# LTM-2405.net
KiCad netlist of a schematic drawn in Altium Designer
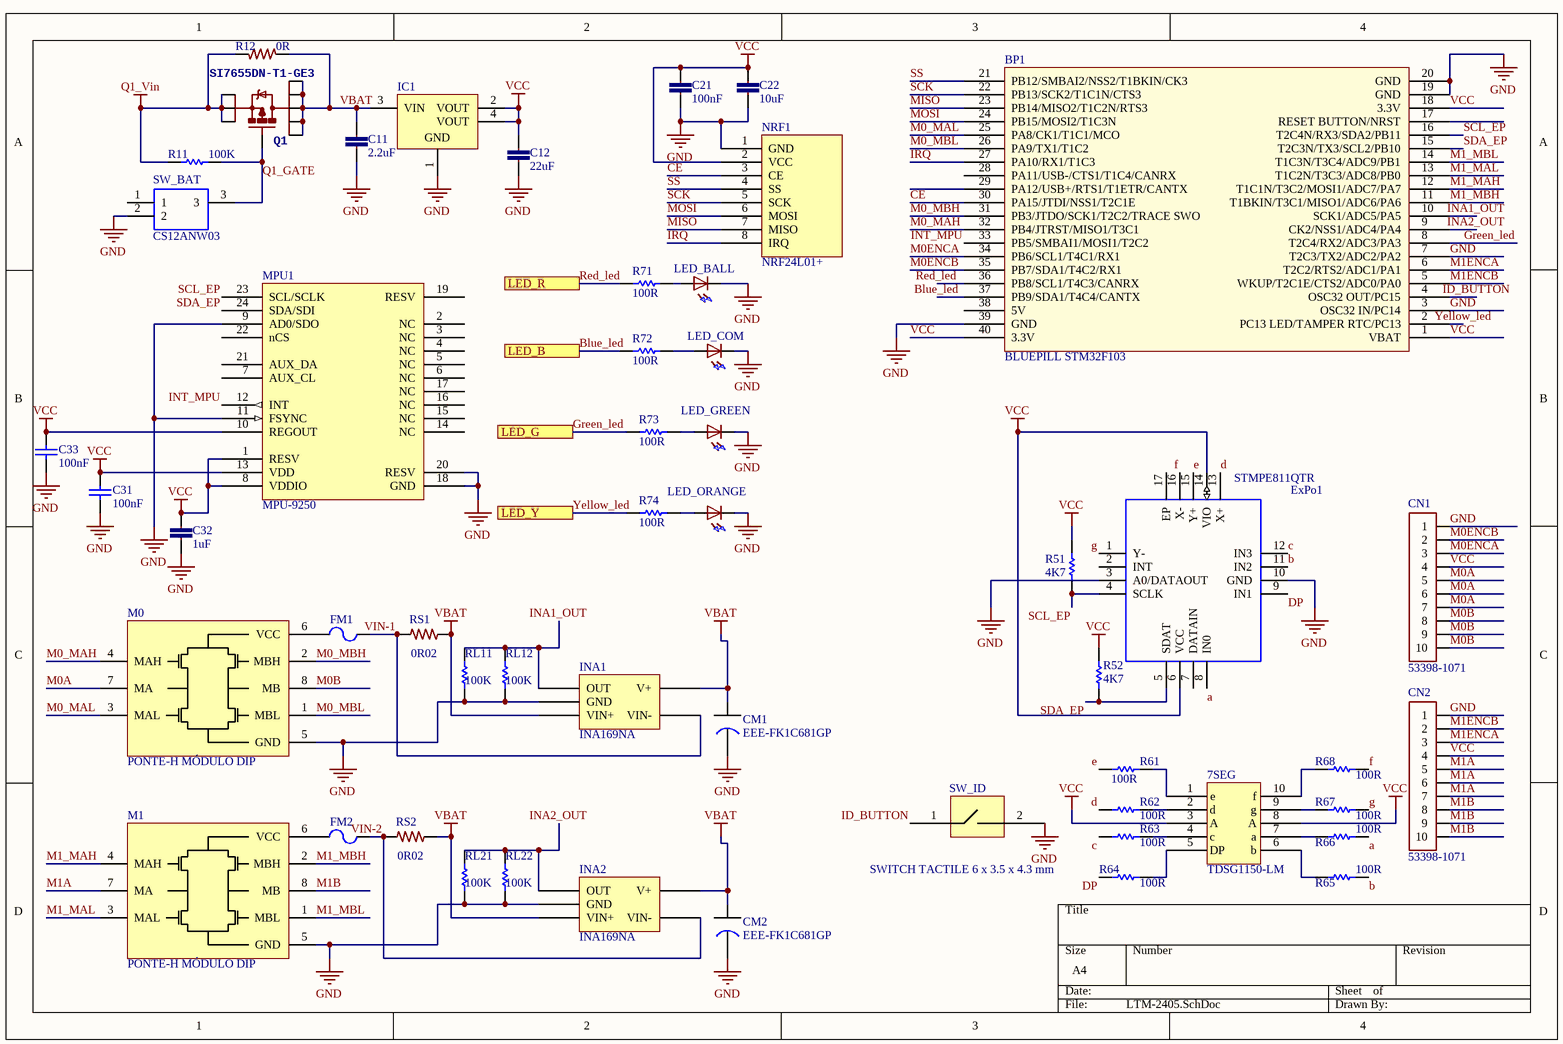
[diagram p0: LTM-2405.SchDoc]

(export (version "E")
  (design (tool "Eeschema 10.0.6"))
  (components
    (comp (ref "7SEG")
      (value "TDSG1150-LM")
      (footprint "7seg-pcb")
      (libsource (lib "7seg") (part "TDSG1150-LM"))
    )
    (comp (ref "BP1")
      (value "BLUEPILL STM32F103")
      (footprint "BLUEPILL-PCB")
      (description "STM32 Blue Pill Development Module")
      (libsource (lib "IMBEL") (part "BLUEPILL-SCH"))
    )
    (comp (ref "C11")
      (value "2.2uF")
      (footprint "1206-CAP")
      (description "CAP CER 2.2UF 50V X7R 1206")
      (fields (field (name "PART NO") "UMK316B7225KL-T"))
      (libsource (lib "IMBEL") (part "CAPACITOR"))
    )
    (comp (ref "C12")
      (value "22uF")
      (footprint "1206-CAP")
      (description "CAP CER 22UF 6.3V 20% X5R 1206")
      (fields (field (name "PART NO") "C3216X5R0J226M085AC"))
      (libsource (lib "IMBEL") (part "CC1206-22uF-6.3V-1"))
    )
    (comp (ref "C21")
      (value "100nF")
      (footprint "0402-CAP")
      (description "CAP CER 0.1UF 50V 10% X7R 0402")
      (fields (field (name "PART NO") "C1005X7R1H104K050BB"))
      (libsource (lib "Personal Vault(migrated)") (part "CAPACITOR"))
    )
    (comp (ref "C22")
      (value "10uF")
      (footprint "1210-CAP")
      (description "CAP CER 10UF 50V 20% X5R 1210")
      (fields (field (name "PART NO") "UMK325BJ106MM"))
      (libsource (lib "") (part "CAPACITOR_1"))
    )
    (comp (ref "C31")
      (value "100nF")
      (footprint "CAPC0402(1005)60_N")
      (description "CAP 100nF 10V ±10% 0402 (1005 Metric) Thickness 0.6mm SMD")
      (fields (field (name "TOLERANCE") "Â±10%"))
      (libsource (lib "Integrated_Library - 26.10.18 - 17.40") (part "CMP-1034-02065-1"))
    )
    (comp (ref "C32")
      (value "1uF")
      (footprint "0402-CAP")
      (description "CAP CER 1UF 6.3V 10% X5R 0402")
      (fields (field (name "PART NO") "JMK105BJ105KV-F"))
      (libsource (lib "IMBEL") (part "CAPACITOR"))
    )
    (comp (ref "C33")
      (value "100nF")
      (footprint "CAPC0402(1005)60_N")
      (description "CAP 100nF 10V ±10% 0402 (1005 Metric) Thickness 0.6mm SMD")
      (fields (field (name "TOLERANCE") "Â±10%"))
      (libsource (lib "Integrated_Library - 26.10.18 - 17.40") (part "CMP-1034-02065-1"))
    )
    (comp (ref "CM1")
      (value "EEE-FK1C681GP")
      (footprint "EEE-FK1C681GP")
      (description "Aluminum Electrolytic Capacitors - SMD Al Lytic Cap SMT FK Series 105C")
      (libsource (lib "Schlib1") (part "CAP AL 680UF/16V"))
    )
    (comp (ref "CM2")
      (value "EEE-FK1C681GP")
      (footprint "EEE-FK1C681GP")
      (description "Aluminum Electrolytic Capacitors - SMD Al Lytic Cap SMT FK Series 105C")
      (libsource (lib "Schlib1") (part "CAP AL 680UF/16V"))
    )
    (comp (ref "CN1")
      (value "53398-1071")
      (footprint "53398-10")
      (description "CONN HEADER 10POS 1.25MM VRT SMD")
      (libsource (lib "IMBEL") (part "CON-10"))
    )
    (comp (ref "CN2")
      (value "53398-1071")
      (footprint "53398-10")
      (description "CONN HEADER 10POS 1.25MM VRT SMD")
      (libsource (lib "IMBEL") (part "CON-10"))
    )
    (comp (ref "ExPo1")
      (value "STMPE811QTR")
      (footprint "QFN50P300X300X100-17N-D")
      (description "Interface - I/O Expanders 8-BIT PORT EXPANDER W/ADV TOUCHSCREEN")
      (fields (field (name "RS PART NUMBER") "1658056"))
      (libsource (lib "STMPE811QTR") (part "STMPE811QTR"))
    )
    (comp (ref "FM1")
      (value "MF-MSMF030-2CT-ND")
      (footprint "RESC4632X16N")
      (description "FUSE PTC RESETTBL .30A 30V 1812")
      (libsource (lib "IMBEL") (part "FUSE-SCH"))
    )
    (comp (ref "FM2")
      (value "MF-MSMF030-2CT-ND")
      (footprint "RESC4632X16N")
      (description "FUSE PTC RESETTBL .30A 30V 1812")
      (libsource (lib "IMBEL") (part "FUSE-SCH"))
    )
    (comp (ref "IC1")
      (value "LD1117S33CTR")
      (footprint "SOT-223_N")
      (description "Fixed Low Drop Positive Voltage Regulator, 3.3V, 4-Pin SOT-223, Tape and Reel")
      (libsource (lib "Altium Content Vault") (part "CMP-0244-00307-1"))
    )
    (comp (ref "INA1")
      (value "INA169NA")
      (footprint "SOT95P280X125-5N")
      (description "IC CURRENT MONITOR 0.5% SOT23-5")
      (libsource (lib "IMBEL") (part "ina169"))
    )
    (comp (ref "INA2")
      (value "INA169NA")
      (footprint "SOT95P280X125-5N")
      (description "IC CURRENT MONITOR 0.5% SOT23-5")
      (libsource (lib "IMBEL") (part "ina169"))
    )
    (comp (ref "LED_BALL")
      (value "LED")
      (footprint "LED-5MM-PCB")
      (description "LED 5MM PTH")
      (libsource (lib "IMBEL") (part "LED"))
    )
    (comp (ref "LED_COM")
      (value "LED")
      (footprint "LED-5MM-PCB")
      (description "LED 5MM PTH")
      (libsource (lib "IMBEL") (part "LED"))
    )
    (comp (ref "LED_GREEN")
      (value "LED")
      (footprint "LED-5MM-PCB")
      (description "LED 5MM PTH")
      (libsource (lib "IMBEL") (part "LED"))
    )
    (comp (ref "LED_ORANGE")
      (value "LED")
      (footprint "LED-5MM-PCB")
      (description "LED 5MM PTH")
      (libsource (lib "IMBEL") (part "LED"))
    )
    (comp (ref "M0")
      (value "PONTE-H MÓDULO DIP")
      (footprint "PONTEH-PCB")
      (description "MÓDULO PONTE H DIP ROBOIME")
      (libsource (lib "IMBEL") (part "PONTEH-SCH"))
    )
    (comp (ref "M1")
      (value "PONTE-H MÓDULO DIP")
      (footprint "PONTEH-PCB")
      (description "MÓDULO PONTE H DIP ROBOIME")
      (libsource (lib "IMBEL") (part "PONTEH-SCH"))
    )
    (comp (ref "MPU1")
      (value "MPU-9250")
      (footprint "MPU-9250")
      (description "IMU ACCEL/GYRO/MAG I2C/SPI 24QFN")
      (libsource (lib "IMBEL") (part "Component_1"))
    )
    (comp (ref "NRF1")
      (value "NRF24L01+")
      (footprint "NRF24L01P-PCB")
      (libsource (lib "IMBEL") (part "NRF24-SCH"))
    )
    (comp (ref "Q1")
      (value "SI7655DN-T1-GE3")
      (footprint "SON8")
      (description "MOSFET P-CH 20V D-S PPAK 1212")
      (libsource (lib "IMBEL") (part "MOSFET-PCHANNEL"))
    )
    (comp (ref "R11")
      (value "100K")
      (footprint "RESC0402(1005)_L")
      (description "100K 0.063W 1% 0402 (1005 Metric)  SMD")
      (fields (field (name "POWER") "0.063 W") (field (name "TOLERANCE") "1 %"))
      (libsource (lib "Integrated_Library - 26.10.18 - 17.11") (part "CMP-1011-00736-1"))
    )
    (comp (ref "R12")
      (value "0R")
      (footprint "0402-RES-HD")
      (description "RES 0.0 OHM 1/16W JUMP 0402 SMD")
      (fields (field (name "PART NO") "CRCW04020000Z0ED"))
      (libsource (lib "IMBEL") (part "RESISTOR"))
    )
    (comp (ref "R51")
      (value "4K7")
      (footprint "RESC0402(1005)_L")
      (description "4K7 0.063W 1% 0402 (1005 Metric)  SMD")
      (fields (field (name "POWER") "0.063 W") (field (name "TOLERANCE") "1 %"))
      (libsource (lib "Integrated_Library - 26.10.18 - 17.46") (part "CMP-1011-00586-1"))
    )
    (comp (ref "R52")
      (value "4K7")
      (footprint "RESC0402(1005)_L")
      (description "4K7 0.063W 1% 0402 (1005 Metric)  SMD")
      (fields (field (name "POWER") "0.063 W") (field (name "TOLERANCE") "1 %"))
      (libsource (lib "Integrated_Library - 26.10.18 - 17.46") (part "CMP-1011-00586-1"))
    )
    (comp (ref "R61")
      (value "100R")
      (footprint "RESC0402(1005)_L")
      (description "100R 0.063W 1% 0402 (1005 Metric)  SMD")
      (fields (field (name "TOLERANCE") "1 %") (field (name "POWER") "0.063 W"))
      (libsource (lib "RES_100R") (part "CMP-1011-00397-1"))
    )
    (comp (ref "R62")
      (value "100R")
      (footprint "RESC0402(1005)_L")
      (description "100R 0.063W 1% 0402 (1005 Metric)  SMD")
      (fields (field (name "TOLERANCE") "1 %") (field (name "POWER") "0.063 W"))
      (libsource (lib "RES_100R") (part "CMP-1011-00397-1"))
    )
    (comp (ref "R63")
      (value "100R")
      (footprint "RESC0402(1005)_L")
      (description "100R 0.063W 1% 0402 (1005 Metric)  SMD")
      (fields (field (name "TOLERANCE") "1 %") (field (name "POWER") "0.063 W"))
      (libsource (lib "RES_100R") (part "CMP-1011-00397-1"))
    )
    (comp (ref "R64")
      (value "100R")
      (footprint "RESC0402(1005)_L")
      (description "100R 0.063W 1% 0402 (1005 Metric)  SMD")
      (fields (field (name "TOLERANCE") "1 %") (field (name "POWER") "0.063 W"))
      (libsource (lib "RES_100R") (part "CMP-1011-00397-1"))
    )
    (comp (ref "R65")
      (value "100R")
      (footprint "RESC0402(1005)_L")
      (description "100R 0.063W 1% 0402 (1005 Metric)  SMD")
      (fields (field (name "TOLERANCE") "1 %") (field (name "POWER") "0.063 W"))
      (libsource (lib "RES_100R") (part "CMP-1011-00397-1"))
    )
    (comp (ref "R66")
      (value "100R")
      (footprint "RESC0402(1005)_L")
      (description "100R 0.063W 1% 0402 (1005 Metric)  SMD")
      (fields (field (name "TOLERANCE") "1 %") (field (name "POWER") "0.063 W"))
      (libsource (lib "RES_100R") (part "CMP-1011-00397-1"))
    )
    (comp (ref "R67")
      (value "100R")
      (footprint "RESC0402(1005)_L")
      (description "100R 0.063W 1% 0402 (1005 Metric)  SMD")
      (fields (field (name "TOLERANCE") "1 %") (field (name "POWER") "0.063 W"))
      (libsource (lib "RES_100R") (part "CMP-1011-00397-1"))
    )
    (comp (ref "R68")
      (value "100R")
      (footprint "RESC0402(1005)_L")
      (description "100R 0.063W 1% 0402 (1005 Metric)  SMD")
      (fields (field (name "TOLERANCE") "1 %") (field (name "POWER") "0.063 W"))
      (libsource (lib "RES_100R") (part "CMP-1011-00397-1"))
    )
    (comp (ref "R71")
      (value "100R")
      (footprint "RESC0402(1005)_L")
      (description "100R 0.063W 1% 0402 (1005 Metric)  SMD")
      (fields (field (name "TOLERANCE") "1 %") (field (name "POWER") "0.063 W"))
      (libsource (lib "RES_100R") (part "CMP-1011-00397-1"))
    )
    (comp (ref "R72")
      (value "100R")
      (footprint "RESC0402(1005)_L")
      (description "100R 0.063W 1% 0402 (1005 Metric)  SMD")
      (fields (field (name "TOLERANCE") "1 %") (field (name "POWER") "0.063 W"))
      (libsource (lib "RES_100R") (part "CMP-1011-00397-1"))
    )
    (comp (ref "R73")
      (value "100R")
      (footprint "RESC0402(1005)_L")
      (description "100R 0.063W 1% 0402 (1005 Metric)  SMD")
      (fields (field (name "TOLERANCE") "1 %") (field (name "POWER") "0.063 W"))
      (libsource (lib "RES_100R") (part "CMP-1011-00397-1"))
    )
    (comp (ref "R74")
      (value "100R")
      (footprint "RESC0402(1005)_L")
      (description "100R 0.063W 1% 0402 (1005 Metric)  SMD")
      (fields (field (name "TOLERANCE") "1 %") (field (name "POWER") "0.063 W"))
      (libsource (lib "RES_100R") (part "CMP-1011-00397-1"))
    )
    (comp (ref "RL11")
      (value "100K")
      (footprint "RESC0402(1005)_L")
      (description "100K 0.063W 1% 0402 (1005 Metric)  SMD")
      (fields (field (name "POWER") "0.063 W") (field (name "TOLERANCE") "1 %"))
      (libsource (lib "Integrated_Library - 26.10.18 - 17.11") (part "CMP-1011-00736-1"))
    )
    (comp (ref "RL12")
      (value "100K")
      (footprint "RESC0402(1005)_L")
      (description "100K 0.063W 1% 0402 (1005 Metric)  SMD")
      (fields (field (name "POWER") "0.063 W") (field (name "TOLERANCE") "1 %"))
      (libsource (lib "Integrated_Library - 26.10.18 - 17.11") (part "CMP-1011-00736-1"))
    )
    (comp (ref "RL21")
      (value "100K")
      (footprint "RESC0402(1005)_L")
      (description "100K 0.063W 1% 0402 (1005 Metric)  SMD")
      (fields (field (name "POWER") "0.063 W") (field (name "TOLERANCE") "1 %"))
      (libsource (lib "Integrated_Library - 26.10.18 - 17.11") (part "CMP-1011-00736-1"))
    )
    (comp (ref "RL22")
      (value "100K")
      (footprint "RESC0402(1005)_L")
      (description "100K 0.063W 1% 0402 (1005 Metric)  SMD")
      (fields (field (name "POWER") "0.063 W") (field (name "TOLERANCE") "1 %"))
      (libsource (lib "Integrated_Library - 26.10.18 - 17.11") (part "CMP-1011-00736-1"))
    )
    (comp (ref "RS1")
      (value "0R02")
      (footprint "2512-RES-HD")
      (description "RES .02 OHM 2W 1% 2512 SMD")
      (fields (field (name "PART NO") "WSL2512R0200FEA18"))
      (libsource (lib "IMBEL") (part "R2512-0R02-4"))
    )
    (comp (ref "RS2")
      (value "0R02")
      (footprint "2512-RES-HD")
      (description "RES .02 OHM 2W 1% 2512 SMD")
      (fields (field (name "PART NO") "WSL2512R0200FEA18"))
      (libsource (lib "IMBEL") (part "R2512-0R02-4"))
    )
    (comp (ref "SW_BAT")
      (value "CS12ANW03")
      (footprint "CS12ANW03")
      (description "NKK SWITCHES - CS12ANW03 - SWITCH, SLIDE, SPDT, 3A, 250V, TH")
      (fields (field (name "RS PART NUMBER") "1251847"))
      (libsource (lib "CS12ANW03") (part "CS12ANW03"))
    )
    (comp (ref "SW_ID")
      (value "SWITCH TACTILE 6 x 3.5 x 4.3 mm")
      (footprint "PCBComponent")
      (description "GRAYHILL TACT,GW,6X3.5,1800T&R,LF Eight, 160g Operating Force, Gull Wing, RoHS Compliant")
      (fields (field (name "PART NO") "95C04A3GWRT"))
      (libsource (lib "Integrated_Library - 26.10.18 - 12.35") (part "95C04A3GWRT.-1"))
    )
  )
  (nets
    (net (code "1") (name "/Blue_led") (class "Default")
      (node (ref "BP1") (pin "37") (pinfunction "PB9/SDA1/T4C4/CANTX_37") (pintype "passive"))
      (node (ref "R72") (pin "1") (pinfunction "1_1") (pintype "passive"))
    )
    (net (code "2") (name "/CE") (class "Default")
      (node (ref "BP1") (pin "30") (pinfunction "PA15/JTDI/NSS1/T2C1E_30") (pintype "passive"))
      (node (ref "NRF1") (pin "3") (pinfunction "CE_3") (pintype "passive"))
    )
    (net (code "3") (name "/DP") (class "Default")
      (node (ref "ExPo1") (pin "9") (pinfunction "IN1_9") (pintype "passive"))
      (node (ref "R64") (pin "1") (pinfunction "1_1") (pintype "passive"))
    )
    (net (code "4") (name "/Green_led") (class "Default")
      (node (ref "BP1") (pin "8") (pinfunction "T2C4/RX2/ADC3/PA3_8") (pintype "passive"))
      (node (ref "R73") (pin "1") (pinfunction "1_1") (pintype "passive"))
    )
    (net (code "5") (name "/ID_BUTTON") (class "Default")
      (node (ref "BP1") (pin "4") (pinfunction "OSC32_OUT/PC15_4") (pintype "passive"))
      (node (ref "SW_ID") (pin "1") (pinfunction "1_1") (pintype "passive"))
    )
    (net (code "6") (name "/INA1_OUT") (class "Default")
      (node (ref "BP1") (pin "10") (pinfunction "SCK1/ADC5/PA5_10") (pintype "passive"))
      (node (ref "INA1") (pin "1") (pinfunction "OUT_1") (pintype "passive"))
      (node (ref "RL11") (pin "2") (pinfunction "2_2") (pintype "passive"))
      (node (ref "RL12") (pin "2") (pinfunction "2_2") (pintype "passive"))
    )
    (net (code "7") (name "/INA2_OUT") (class "Default")
      (node (ref "BP1") (pin "9") (pinfunction "CK2/NSS1/ADC4/PA4_9") (pintype "passive"))
      (node (ref "INA2") (pin "1") (pinfunction "OUT_1") (pintype "passive"))
      (node (ref "RL21") (pin "2") (pinfunction "2_2") (pintype "passive"))
      (node (ref "RL22") (pin "2") (pinfunction "2_2") (pintype "passive"))
    )
    (net (code "8") (name "/INT_MPU") (class "Default")
      (node (ref "BP1") (pin "33") (pinfunction "PB5/SMBAI1/MOSI1/T2C2_33") (pintype "passive"))
      (node (ref "MPU1") (pin "12") (pinfunction "INT_12") (pintype "output"))
    )
    (net (code "9") (name "/IRQ") (class "Default")
      (node (ref "BP1") (pin "27") (pinfunction "PA10/RX1/T1C3_27") (pintype "passive"))
      (node (ref "NRF1") (pin "8") (pinfunction "IRQ_8") (pintype "passive"))
    )
    (net (code "10") (name "/M0A") (class "Default")
      (node (ref "CN1") (pin "5") (pinfunction "5_5") (pintype "passive"))
      (node (ref "CN1") (pin "6") (pinfunction "6_6") (pintype "passive"))
      (node (ref "CN1") (pin "7") (pinfunction "7_7") (pintype "passive"))
      (node (ref "M0") (pin "7") (pinfunction "MA_7") (pintype "passive"))
    )
    (net (code "11") (name "/M0B") (class "Default")
      (node (ref "CN1") (pin "10") (pinfunction "10_10") (pintype "passive"))
      (node (ref "CN1") (pin "8") (pinfunction "8_8") (pintype "passive"))
      (node (ref "CN1") (pin "9") (pinfunction "9_9") (pintype "passive"))
      (node (ref "M0") (pin "8") (pinfunction "MB_8") (pintype "passive"))
    )
    (net (code "12") (name "/M0ENCA") (class "Default")
      (node (ref "BP1") (pin "34") (pinfunction "PB6/SCL1/T4C1/RX1_34") (pintype "passive"))
      (node (ref "CN1") (pin "3") (pinfunction "3_3") (pintype "passive"))
    )
    (net (code "13") (name "/M0ENCB") (class "Default")
      (node (ref "BP1") (pin "35") (pinfunction "PB7/SDA1/T4C2/RX1_35") (pintype "passive"))
      (node (ref "CN1") (pin "2") (pinfunction "2_2") (pintype "passive"))
    )
    (net (code "14") (name "/M0_MAH") (class "Default")
      (node (ref "BP1") (pin "32") (pinfunction "PB4/JTRST/MISO1/T3C1_32") (pintype "passive"))
      (node (ref "M0") (pin "4") (pinfunction "MAH_4") (pintype "passive"))
    )
    (net (code "15") (name "/M0_MAL") (class "Default")
      (node (ref "BP1") (pin "25") (pinfunction "PA8/CK1/T1C1/MCO_25") (pintype "passive"))
      (node (ref "M0") (pin "3") (pinfunction "MAL_3") (pintype "passive"))
    )
    (net (code "16") (name "/M0_MBH") (class "Default")
      (node (ref "BP1") (pin "31") (pinfunction "PB3/JTDO/SCK1/T2C2/TRACE_SWO_31") (pintype "passive"))
      (node (ref "M0") (pin "2") (pinfunction "MBH_2") (pintype "passive"))
    )
    (net (code "17") (name "/M0_MBL") (class "Default")
      (node (ref "BP1") (pin "26") (pinfunction "PA9/TX1/T1C2_26") (pintype "passive"))
      (node (ref "M0") (pin "1") (pinfunction "MBL_1") (pintype "passive"))
    )
    (net (code "18") (name "/M1A") (class "Default")
      (node (ref "CN2") (pin "5") (pinfunction "5_5") (pintype "passive"))
      (node (ref "CN2") (pin "6") (pinfunction "6_6") (pintype "passive"))
      (node (ref "CN2") (pin "7") (pinfunction "7_7") (pintype "passive"))
      (node (ref "M1") (pin "7") (pinfunction "MA_7") (pintype "passive"))
    )
    (net (code "19") (name "/M1B") (class "Default")
      (node (ref "CN2") (pin "10") (pinfunction "10_10") (pintype "passive"))
      (node (ref "CN2") (pin "8") (pinfunction "8_8") (pintype "passive"))
      (node (ref "CN2") (pin "9") (pinfunction "9_9") (pintype "passive"))
      (node (ref "M1") (pin "8") (pinfunction "MB_8") (pintype "passive"))
    )
    (net (code "20") (name "/M1ENCA") (class "Default")
      (node (ref "BP1") (pin "6") (pinfunction "T2C2/RTS2/ADC1/PA1_6") (pintype "passive"))
      (node (ref "CN2") (pin "3") (pinfunction "3_3") (pintype "passive"))
    )
    (net (code "21") (name "/M1ENCB") (class "Default")
      (node (ref "BP1") (pin "5") (pinfunction "WKUP/T2C1E/CTS2/ADC0/PA0_5") (pintype "passive"))
      (node (ref "CN2") (pin "2") (pinfunction "2_2") (pintype "passive"))
    )
    (net (code "22") (name "/M1_MAH") (class "Default")
      (node (ref "BP1") (pin "12") (pinfunction "T1C1N/T3C2/MOSI1/ADC7/PA7_12") (pintype "passive"))
      (node (ref "M1") (pin "4") (pinfunction "MAH_4") (pintype "passive"))
    )
    (net (code "23") (name "/M1_MAL") (class "Default")
      (node (ref "BP1") (pin "13") (pinfunction "T1C2N/T3C3/ADC8/PB0_13") (pintype "passive"))
      (node (ref "M1") (pin "3") (pinfunction "MAL_3") (pintype "passive"))
    )
    (net (code "24") (name "/M1_MBH") (class "Default")
      (node (ref "BP1") (pin "11") (pinfunction "T1BKIN/T3C1/MISO1/ADC6/PA6_11") (pintype "passive"))
      (node (ref "M1") (pin "2") (pinfunction "MBH_2") (pintype "passive"))
    )
    (net (code "25") (name "/M1_MBL") (class "Default")
      (node (ref "BP1") (pin "14") (pinfunction "T1C3N/T3C4/ADC9/PB1_14") (pintype "passive"))
      (node (ref "M1") (pin "1") (pinfunction "MBL_1") (pintype "passive"))
    )
    (net (code "26") (name "/MISO") (class "Default")
      (node (ref "BP1") (pin "23") (pinfunction "PB14/MISO2/T1C2N/RTS3_23") (pintype "passive"))
      (node (ref "NRF1") (pin "7") (pinfunction "MISO_7") (pintype "passive"))
    )
    (net (code "27") (name "/MOSI") (class "Default")
      (node (ref "BP1") (pin "24") (pinfunction "PB15/MOSI2/T1C3N_24") (pintype "passive"))
      (node (ref "NRF1") (pin "6") (pinfunction "MOSI_6") (pintype "passive"))
    )
    (net (code "28") (name "/Q1_GATE") (class "Default")
      (node (ref "Q1") (pin "4") (pinfunction "G_4") (pintype "passive"))
      (node (ref "R11") (pin "2") (pinfunction "2_2") (pintype "passive"))
      (node (ref "SW_BAT") (pin "3") (pinfunction "3_3") (pintype "passive"))
    )
    (net (code "29") (name "/Red_led") (class "Default")
      (node (ref "BP1") (pin "36") (pinfunction "PB8/SCL1/T4C3/CANRX_36") (pintype "passive"))
      (node (ref "R71") (pin "1") (pinfunction "1_1") (pintype "passive"))
    )
    (net (code "30") (name "/SCK") (class "Default")
      (node (ref "BP1") (pin "22") (pinfunction "PB13/SCK2/T1C1N/CTS3_22") (pintype "passive"))
      (node (ref "NRF1") (pin "5") (pinfunction "SCK_5") (pintype "passive"))
    )
    (net (code "31") (name "/SCL_EP") (class "Default")
      (node (ref "BP1") (pin "16") (pinfunction "T2C4N/RX3/SDA2/PB11_16") (pintype "passive"))
      (node (ref "ExPo1") (pin "4") (pinfunction "SCLK_4") (pintype "passive"))
      (node (ref "MPU1") (pin "23") (pinfunction "SCL/SCLK_23") (pintype "passive"))
      (node (ref "R51") (pin "1") (pinfunction "1_1") (pintype "passive"))
    )
    (net (code "32") (name "/SDA_EP") (class "Default")
      (node (ref "BP1") (pin "15") (pinfunction "T2C3N/TX3/SCL2/PB10_15") (pintype "passive"))
      (node (ref "ExPo1") (pin "5") (pinfunction "SDAT_5") (pintype "passive"))
      (node (ref "MPU1") (pin "24") (pinfunction "SDA/SDI_24") (pintype "passive"))
      (node (ref "R52") (pin "1") (pinfunction "1_1") (pintype "passive"))
    )
    (net (code "33") (name "/SS") (class "Default")
      (node (ref "BP1") (pin "21") (pinfunction "PB12/SMBAI2/NSS2/T1BKIN/CK3_21") (pintype "passive"))
      (node (ref "NRF1") (pin "4") (pinfunction "SS_4") (pintype "passive"))
    )
    (net (code "34") (name "/VIN-1") (class "Default")
      (node (ref "FM1") (pin "1") (pinfunction "1_1") (pintype "passive"))
      (node (ref "INA1") (pin "5") (pinfunction "VIN-_5") (pintype "passive"))
      (node (ref "RS1") (pin "2") (pinfunction "2_2") (pintype "passive"))
    )
    (net (code "35") (name "/VIN-2") (class "Default")
      (node (ref "FM2") (pin "1") (pinfunction "1_1") (pintype "passive"))
      (node (ref "INA2") (pin "5") (pinfunction "VIN-_5") (pintype "passive"))
      (node (ref "RS2") (pin "2") (pinfunction "2_2") (pintype "passive"))
    )
    (net (code "36") (name "/Yellow_led") (class "Default")
      (node (ref "BP1") (pin "2") (pinfunction "PC13_LED/TAMPER_RTC/PC13_2") (pintype "passive"))
      (node (ref "R74") (pin "1") (pinfunction "1_1") (pintype "passive"))
    )
    (net (code "37") (name "/a") (class "Default")
      (node (ref "ExPo1") (pin "8") (pinfunction "IN0_8") (pintype "passive"))
      (node (ref "R66") (pin "2") (pinfunction "2_2") (pintype "passive"))
    )
    (net (code "38") (name "/b") (class "Default")
      (node (ref "ExPo1") (pin "11") (pinfunction "IN2_11") (pintype "passive"))
      (node (ref "R65") (pin "2") (pinfunction "2_2") (pintype "passive"))
    )
    (net (code "39") (name "/c") (class "Default")
      (node (ref "ExPo1") (pin "12") (pinfunction "IN3_12") (pintype "passive"))
      (node (ref "R63") (pin "1") (pinfunction "1_1") (pintype "passive"))
    )
    (net (code "40") (name "/d") (class "Default")
      (node (ref "ExPo1") (pin "13") (pinfunction "X+_13") (pintype "passive"))
      (node (ref "R62") (pin "1") (pinfunction "1_1") (pintype "passive"))
    )
    (net (code "41") (name "/e") (class "Default")
      (node (ref "ExPo1") (pin "15") (pinfunction "Y+_15") (pintype "passive"))
      (node (ref "R61") (pin "1") (pinfunction "1_1") (pintype "passive"))
    )
    (net (code "42") (name "/f") (class "Default")
      (node (ref "ExPo1") (pin "16") (pinfunction "X-_16") (pintype "passive"))
      (node (ref "R68") (pin "2") (pinfunction "2_2") (pintype "passive"))
    )
    (net (code "43") (name "/g") (class "Default")
      (node (ref "ExPo1") (pin "1") (pinfunction "Y-_1") (pintype "passive"))
      (node (ref "R67") (pin "2") (pinfunction "2_2") (pintype "passive"))
    )
    (net (code "44") (name "GND") (class "Default")
      (node (ref "BP1") (pin "19") (pinfunction "GND_19") (pintype "passive"))
      (node (ref "BP1") (pin "20") (pinfunction "GND_20") (pintype "passive"))
      (node (ref "BP1") (pin "3") (pinfunction "OSC32_IN/PC14_3") (pintype "passive"))
      (node (ref "BP1") (pin "39") (pinfunction "GND_39") (pintype "passive"))
      (node (ref "BP1") (pin "7") (pinfunction "T2C3/TX2/ADC2/PA2_7") (pintype "passive"))
      (node (ref "C11") (pin "2") (pinfunction "2_2") (pintype "passive"))
      (node (ref "C12") (pin "1") (pinfunction "1_1") (pintype "passive"))
      (node (ref "C21") (pin "2") (pinfunction "2_2") (pintype "passive"))
      (node (ref "C22") (pin "1") (pinfunction "1_1") (pintype "passive"))
      (node (ref "C31") (pin "1") (pinfunction "1_1") (pintype "passive"))
      (node (ref "C32") (pin "2") (pinfunction "2_2") (pintype "passive"))
      (node (ref "C33") (pin "1") (pinfunction "1_1") (pintype "passive"))
      (node (ref "CM1") (pin "2") (pinfunction "2_2") (pintype "passive"))
      (node (ref "CM2") (pin "2") (pinfunction "2_2") (pintype "passive"))
      (node (ref "CN1") (pin "1") (pinfunction "1_1") (pintype "passive"))
      (node (ref "CN2") (pin "1") (pinfunction "1_1") (pintype "passive"))
      (node (ref "ExPo1") (pin "10") (pinfunction "GND_10") (pintype "passive"))
      (node (ref "ExPo1") (pin "3") (pinfunction "A0/DATAOUT_3") (pintype "passive"))
      (node (ref "IC1") (pin "1") (pinfunction "GND_1") (pintype "power_in"))
      (node (ref "INA1") (pin "2") (pinfunction "GND_2") (pintype "passive"))
      (node (ref "INA2") (pin "2") (pinfunction "GND_2") (pintype "passive"))
      (node (ref "LED_BALL") (pin "1") (pinfunction "K_1") (pintype "passive"))
      (node (ref "LED_COM") (pin "1") (pinfunction "K_1") (pintype "passive"))
      (node (ref "LED_GREEN") (pin "1") (pinfunction "K_1") (pintype "passive"))
      (node (ref "LED_ORANGE") (pin "1") (pinfunction "K_1") (pintype "passive"))
      (node (ref "M0") (pin "5") (pinfunction "GND_5") (pintype "passive"))
      (node (ref "M1") (pin "5") (pinfunction "GND_5") (pintype "passive"))
      (node (ref "MPU1") (pin "11") (pinfunction "FSYNC_11") (pintype "input"))
      (node (ref "MPU1") (pin "18") (pinfunction "GND_18") (pintype "power_in"))
      (node (ref "MPU1") (pin "20") (pinfunction "RESV_20") (pintype "passive"))
      (node (ref "MPU1") (pin "9") (pinfunction "AD0/SDO_9") (pintype "passive"))
      (node (ref "NRF1") (pin "1") (pinfunction "GND_1") (pintype "passive"))
      (node (ref "RL11") (pin "1") (pinfunction "1_1") (pintype "passive"))
      (node (ref "RL12") (pin "1") (pinfunction "1_1") (pintype "passive"))
      (node (ref "RL21") (pin "1") (pinfunction "1_1") (pintype "passive"))
      (node (ref "RL22") (pin "1") (pinfunction "1_1") (pintype "passive"))
      (node (ref "SW_BAT") (pin "2") (pinfunction "2_2") (pintype "passive"))
      (node (ref "SW_ID") (pin "2") (pinfunction "2_2") (pintype "passive"))
    )
    (net (code "45") (name "Net-(7SEG-DP)") (class "Default")
      (node (ref "7SEG") (pin "5") (pinfunction "DP_5") (pintype "passive"))
      (node (ref "R64") (pin "2") (pinfunction "2_2") (pintype "passive"))
    )
    (net (code "46") (name "Net-(7SEG-a)") (class "Default")
      (node (ref "7SEG") (pin "7") (pinfunction "a_7") (pintype "passive"))
      (node (ref "R66") (pin "1") (pinfunction "1_1") (pintype "passive"))
    )
    (net (code "47") (name "Net-(7SEG-b)") (class "Default")
      (node (ref "7SEG") (pin "6") (pinfunction "b_6") (pintype "passive"))
      (node (ref "R65") (pin "1") (pinfunction "1_1") (pintype "passive"))
    )
    (net (code "48") (name "Net-(7SEG-c)") (class "Default")
      (node (ref "7SEG") (pin "4") (pinfunction "c_4") (pintype "passive"))
      (node (ref "R63") (pin "2") (pinfunction "2_2") (pintype "passive"))
    )
    (net (code "49") (name "Net-(7SEG-d)") (class "Default")
      (node (ref "7SEG") (pin "2") (pinfunction "d_2") (pintype "passive"))
      (node (ref "R62") (pin "2") (pinfunction "2_2") (pintype "passive"))
    )
    (net (code "50") (name "Net-(7SEG-e)") (class "Default")
      (node (ref "7SEG") (pin "1") (pinfunction "e_1") (pintype "passive"))
      (node (ref "R61") (pin "2") (pinfunction "2_2") (pintype "passive"))
    )
    (net (code "51") (name "Net-(7SEG-f)") (class "Default")
      (node (ref "7SEG") (pin "10") (pinfunction "f_10") (pintype "passive"))
      (node (ref "R68") (pin "1") (pinfunction "1_1") (pintype "passive"))
    )
    (net (code "52") (name "Net-(7SEG-g)") (class "Default")
      (node (ref "7SEG") (pin "9") (pinfunction "g_9") (pintype "passive"))
      (node (ref "R67") (pin "1") (pinfunction "1_1") (pintype "passive"))
    )
    (net (code "53") (name "Net-(LED_BALL-A)") (class "Default")
      (node (ref "LED_BALL") (pin "2") (pinfunction "A_2") (pintype "passive"))
      (node (ref "R71") (pin "2") (pinfunction "2_2") (pintype "passive"))
    )
    (net (code "54") (name "Net-(LED_COM-A)") (class "Default")
      (node (ref "LED_COM") (pin "2") (pinfunction "A_2") (pintype "passive"))
      (node (ref "R72") (pin "2") (pinfunction "2_2") (pintype "passive"))
    )
    (net (code "55") (name "Net-(LED_GREEN-A)") (class "Default")
      (node (ref "LED_GREEN") (pin "2") (pinfunction "A_2") (pintype "passive"))
      (node (ref "R73") (pin "2") (pinfunction "2_2") (pintype "passive"))
    )
    (net (code "56") (name "Net-(LED_ORANGE-A)") (class "Default")
      (node (ref "LED_ORANGE") (pin "2") (pinfunction "A_2") (pintype "passive"))
      (node (ref "R74") (pin "2") (pinfunction "2_2") (pintype "passive"))
    )
    (net (code "57") (name "Net-(M0-VCC)") (class "Default")
      (node (ref "FM1") (pin "2") (pinfunction "2_2") (pintype "passive"))
      (node (ref "M0") (pin "6") (pinfunction "VCC_6") (pintype "passive"))
    )
    (net (code "58") (name "Net-(M1-VCC)") (class "Default")
      (node (ref "FM2") (pin "2") (pinfunction "2_2") (pintype "passive"))
      (node (ref "M1") (pin "6") (pinfunction "VCC_6") (pintype "passive"))
    )
    (net (code "59") (name "Q1_Vin") (class "Default")
      (node (ref "Q1") (pin "1") (pinfunction "S_1") (pintype "passive"))
      (node (ref "Q1") (pin "2") (pinfunction "S_2") (pintype "passive"))
      (node (ref "Q1") (pin "3") (pinfunction "S_3") (pintype "passive"))
      (node (ref "R11") (pin "1") (pinfunction "1_1") (pintype "passive"))
      (node (ref "R12") (pin "2") (pinfunction "2_2") (pintype "passive"))
    )
    (net (code "60") (name "VBAT") (class "Default")
      (node (ref "C11") (pin "1") (pinfunction "1_1") (pintype "passive"))
      (node (ref "CM1") (pin "1") (pinfunction "1_1") (pintype "passive"))
      (node (ref "CM2") (pin "1") (pinfunction "1_1") (pintype "passive"))
      (node (ref "IC1") (pin "3") (pinfunction "VIN_3") (pintype "power_in"))
      (node (ref "INA1") (pin "3") (pinfunction "VIN+_3") (pintype "passive"))
      (node (ref "INA1") (pin "4") (pinfunction "V+_4") (pintype "passive"))
      (node (ref "INA2") (pin "3") (pinfunction "VIN+_3") (pintype "passive"))
      (node (ref "INA2") (pin "4") (pinfunction "V+_4") (pintype "passive"))
      (node (ref "Q1") (pin "5") (pinfunction "D_5") (pintype "passive"))
      (node (ref "Q1") (pin "6") (pinfunction "D_6") (pintype "passive"))
      (node (ref "Q1") (pin "7") (pinfunction "D_7") (pintype "passive"))
      (node (ref "Q1") (pin "8") (pinfunction "D_8") (pintype "passive"))
      (node (ref "Q1") (pin "9") (pinfunction "D_9") (pintype "passive"))
      (node (ref "R12") (pin "1") (pinfunction "1_1") (pintype "passive"))
      (node (ref "RS1") (pin "1") (pinfunction "1_1") (pintype "passive"))
      (node (ref "RS2") (pin "1") (pinfunction "1_1") (pintype "passive"))
    )
    (net (code "61") (name "VCC") (class "Default")
      (node (ref "7SEG") (pin "3") (pinfunction "A_3") (pintype "passive"))
      (node (ref "7SEG") (pin "8") (pinfunction "A_8") (pintype "passive"))
      (node (ref "BP1") (pin "1") (pinfunction "VBAT_1") (pintype "passive"))
      (node (ref "BP1") (pin "18") (pinfunction "3.3V_18") (pintype "passive"))
      (node (ref "BP1") (pin "40") (pinfunction "3.3V_40") (pintype "passive"))
      (node (ref "C12") (pin "2") (pinfunction "2_2") (pintype "passive"))
      (node (ref "C21") (pin "1") (pinfunction "1_1") (pintype "passive"))
      (node (ref "C22") (pin "2") (pinfunction "2_2") (pintype "passive"))
      (node (ref "C31") (pin "2") (pinfunction "2_2") (pintype "passive"))
      (node (ref "C32") (pin "1") (pinfunction "1_1") (pintype "passive"))
      (node (ref "C33") (pin "2") (pinfunction "2_2") (pintype "passive"))
      (node (ref "CN1") (pin "4") (pinfunction "4_4") (pintype "passive"))
      (node (ref "CN2") (pin "4") (pinfunction "4_4") (pintype "passive"))
      (node (ref "ExPo1") (pin "14") (pinfunction "VIO_14") (pintype "bidirectional"))
      (node (ref "ExPo1") (pin "6") (pinfunction "VCC_6") (pintype "power_in"))
      (node (ref "IC1") (pin "2") (pinfunction "VOUT_2") (pintype "power_in"))
      (node (ref "IC1") (pin "4") (pinfunction "VOUT_4") (pintype "power_in"))
      (node (ref "MPU1") (pin "1") (pinfunction "RESV_1") (pintype "passive"))
      (node (ref "MPU1") (pin "10") (pinfunction "REGOUT_10") (pintype "passive"))
      (node (ref "MPU1") (pin "13") (pinfunction "VDD_13") (pintype "power_in"))
      (node (ref "MPU1") (pin "8") (pinfunction "VDDIO_8") (pintype "power_in"))
      (node (ref "NRF1") (pin "2") (pinfunction "VCC_2") (pintype "passive"))
      (node (ref "R51") (pin "2") (pinfunction "2_2") (pintype "passive"))
      (node (ref "R52") (pin "2") (pinfunction "2_2") (pintype "passive"))
    )
    (net (code "62") (name "unconnected-(BP1-5V-Pad38)") (class "Default")
      (node (ref "BP1") (pin "38") (pinfunction "5V_38") (pintype "passive"))
    )
    (net (code "63") (name "unconnected-(BP1-PA11{slash}USB-{slash}CTS1{slash}T1C4{slash}CANRX-Pad28)") (class "Default")
      (node (ref "BP1") (pin "28") (pinfunction "PA11/USB-/CTS1/T1C4/CANRX_28") (pintype "passive"))
    )
    (net (code "64") (name "unconnected-(BP1-PA12{slash}USB+{slash}RTS1{slash}T1ETR{slash}CANTX-Pad29)") (class "Default")
      (node (ref "BP1") (pin "29") (pinfunction "PA12/USB+/RTS1/T1ETR/CANTX_29") (pintype "passive"))
    )
    (net (code "65") (name "unconnected-(BP1-RESET_BUTTON{slash}NRST-Pad17)") (class "Default")
      (node (ref "BP1") (pin "17") (pinfunction "RESET_BUTTON/NRST_17") (pintype "passive"))
    )
    (net (code "66") (name "unconnected-(ExPo1-DATAIN-Pad7)") (class "Default")
      (node (ref "ExPo1") (pin "7") (pinfunction "DATAIN_7") (pintype "passive"))
    )
    (net (code "67") (name "unconnected-(ExPo1-EP-Pad17)") (class "Default")
      (node (ref "ExPo1") (pin "17") (pinfunction "EP_17") (pintype "passive"))
    )
    (net (code "68") (name "unconnected-(ExPo1-INT-Pad2)") (class "Default")
      (node (ref "ExPo1") (pin "2") (pinfunction "INT_2") (pintype "passive"))
    )
    (net (code "69") (name "unconnected-(MPU1-AUX_CL-Pad7)") (class "Default")
      (node (ref "MPU1") (pin "7") (pinfunction "AUX_CL_7") (pintype "passive"))
    )
    (net (code "70") (name "unconnected-(MPU1-AUX_DA-Pad21)") (class "Default")
      (node (ref "MPU1") (pin "21") (pinfunction "AUX_DA_21") (pintype "passive"))
    )
    (net (code "71") (name "unconnected-(MPU1-NC-Pad2)") (class "Default")
      (node (ref "MPU1") (pin "2") (pinfunction "NC_2") (pintype "passive"))
    )
    (net (code "72") (name "unconnected-(MPU1-NC-Pad3)") (class "Default")
      (node (ref "MPU1") (pin "3") (pinfunction "NC_3") (pintype "passive"))
    )
    (net (code "73") (name "unconnected-(MPU1-NC-Pad4)") (class "Default")
      (node (ref "MPU1") (pin "4") (pinfunction "NC_4") (pintype "passive"))
    )
    (net (code "74") (name "unconnected-(MPU1-NC-Pad5)") (class "Default")
      (node (ref "MPU1") (pin "5") (pinfunction "NC_5") (pintype "passive"))
    )
    (net (code "75") (name "unconnected-(MPU1-NC-Pad6)") (class "Default")
      (node (ref "MPU1") (pin "6") (pinfunction "NC_6") (pintype "passive"))
    )
    (net (code "76") (name "unconnected-(MPU1-NC-Pad14)") (class "Default")
      (node (ref "MPU1") (pin "14") (pinfunction "NC_14") (pintype "passive"))
    )
    (net (code "77") (name "unconnected-(MPU1-NC-Pad15)") (class "Default")
      (node (ref "MPU1") (pin "15") (pinfunction "NC_15") (pintype "passive"))
    )
    (net (code "78") (name "unconnected-(MPU1-NC-Pad16)") (class "Default")
      (node (ref "MPU1") (pin "16") (pinfunction "NC_16") (pintype "passive"))
    )
    (net (code "79") (name "unconnected-(MPU1-NC-Pad17)") (class "Default")
      (node (ref "MPU1") (pin "17") (pinfunction "NC_17") (pintype "passive"))
    )
    (net (code "80") (name "unconnected-(MPU1-RESV-Pad19)") (class "Default")
      (node (ref "MPU1") (pin "19") (pinfunction "RESV_19") (pintype "passive"))
    )
    (net (code "81") (name "unconnected-(MPU1-nCS-Pad22)") (class "Default")
      (node (ref "MPU1") (pin "22") (pinfunction "nCS_22") (pintype "passive"))
    )
    (net (code "82") (name "unconnected-(SW_BAT-Pad1)") (class "Default")
      (node (ref "SW_BAT") (pin "1") (pinfunction "1_1") (pintype "passive"))
    )
  )
)
